# IOTBeev0_11.net
KiCad netlist of a schematic drawn in EAGLE
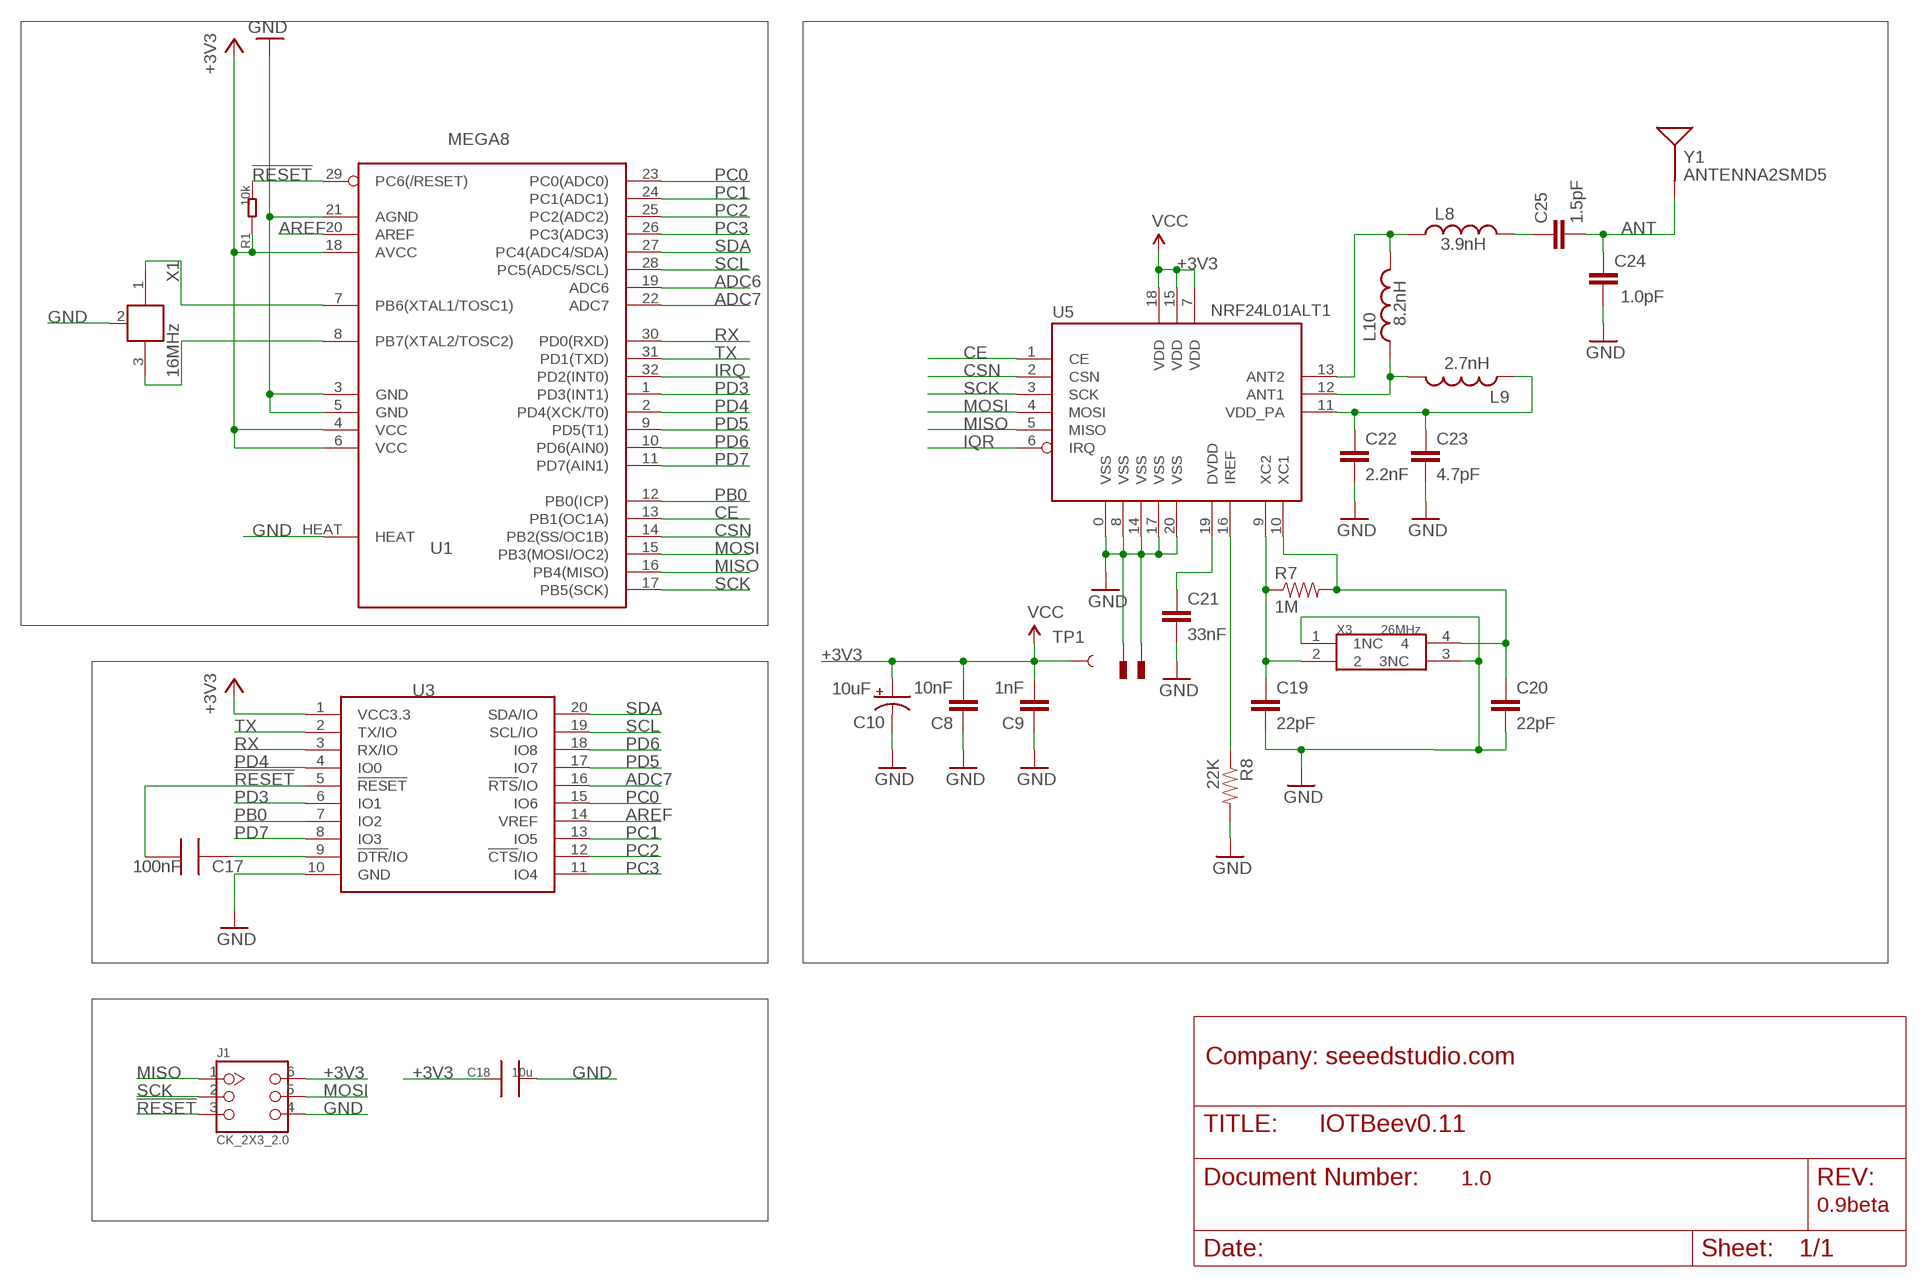
[diagram p0: schematic, sheet 1]

(export (version "E")
  (design (tool "Eeschema 10.0.6"))
  (components
    (comp (ref "C8")
      (value "10nF")
      (footprint "eagle-import:0402-CAP")
      (libsource (lib "eagle-import") (part "CAP0402-CAP"))
    )
    (comp (ref "C9")
      (value "1nF")
      (footprint "eagle-import:0402-CAP")
      (libsource (lib "eagle-import") (part "CAP0402-CAP"))
    )
    (comp (ref "C10")
      (value "10uF")
      (footprint "eagle-import:EIA3528")
      (libsource (lib "eagle-import") (part "CAP_POL3528"))
    )
    (comp (ref "C17")
      (value "100nF")
      (footprint "eagle-import:0603_S")
      (libsource (lib "eagle-import") (part "C0603_S"))
    )
    (comp (ref "C18")
      (value "10u")
      (footprint "eagle-import:0805")
      (libsource (lib "eagle-import") (part "C0805"))
    )
    (comp (ref "C19")
      (value "22pF")
      (footprint "eagle-import:0402-CAP")
      (libsource (lib "eagle-import") (part "CAP0402-CAP"))
    )
    (comp (ref "C20")
      (value "22pF")
      (footprint "eagle-import:0402-CAP")
      (libsource (lib "eagle-import") (part "CAP0402-CAP"))
    )
    (comp (ref "C21")
      (value "33nF")
      (footprint "eagle-import:0402-CAP")
      (libsource (lib "eagle-import") (part "CAP0402-CAP"))
    )
    (comp (ref "C22")
      (value "2.2nF")
      (footprint "eagle-import:0402-CAP")
      (libsource (lib "eagle-import") (part "CAP0402-CAP"))
    )
    (comp (ref "C23")
      (value "4.7pF")
      (footprint "eagle-import:0402-CAP")
      (libsource (lib "eagle-import") (part "CAP0402-CAP"))
    )
    (comp (ref "C24")
      (value "1.0pF")
      (footprint "eagle-import:0402-CAP")
      (libsource (lib "eagle-import") (part "CAP0402-CAP"))
    )
    (comp (ref "C25")
      (value "1.5pF")
      (footprint "eagle-import:0402-CAP")
      (libsource (lib "eagle-import") (part "CAP0402-CAP"))
    )
    (comp (ref "J1")
      (value "CK_2X3_2.0")
      (footprint "eagle-import:CK_2X3_2.0")
      (libsource (lib "eagle-import") (part "CK_2X3_2.0"))
    )
    (comp (ref "L8")
      (value "3.9nH")
      (footprint "eagle-import:C0402")
      (libsource (lib "eagle-import") (part "INDUCTOR0402"))
    )
    (comp (ref "L9")
      (value "2.7nH")
      (footprint "eagle-import:C0402")
      (libsource (lib "eagle-import") (part "INDUCTOR0402"))
    )
    (comp (ref "L10")
      (value "8.2nH")
      (footprint "eagle-import:C0402")
      (libsource (lib "eagle-import") (part "INDUCTOR0402"))
    )
    (comp (ref "R1")
      (value "10k")
      (footprint "eagle-import:0603_S")
      (libsource (lib "eagle-import") (part "R0603_S"))
    )
    (comp (ref "R7")
      (value "1M")
      (footprint "eagle-import:0402-RES")
      (libsource (lib "eagle-import") (part "RESISTOR0402-RES"))
    )
    (comp (ref "R8")
      (value "22K")
      (footprint "eagle-import:0402-RES")
      (libsource (lib "eagle-import") (part "RESISTOR0402-RES"))
    )
    (comp (ref "TP1")
      (value "TEST-POINT3X5")
      (footprint "eagle-import:PAD.03X.05")
      (libsource (lib "eagle-import") (part "TEST-POINT3X5"))
    )
    (comp (ref "U$2")
      (value "PAD")
      (footprint "eagle-import:PAD-0.008")
      (libsource (lib "eagle-import") (part "PAD"))
    )
    (comp (ref "U$4")
      (value "PAD")
      (footprint "eagle-import:PAD-0.008")
      (libsource (lib "eagle-import") (part "PAD"))
    )
    (comp (ref "U1")
      (value "MEGA8")
      (footprint "eagle-import:MLF32X")
      (libsource (lib "eagle-import") (part "MEGA8"))
    )
    (comp (ref "U3")
      (value "BEE-OPENBEE-BTSMD")
      (footprint "eagle-import:20P-SMD-2.0-BT")
      (libsource (lib "eagle-import") (part "BEE-OPENBEE-BTSMD"))
    )
    (comp (ref "U5")
      (value "NRF24L01ALT1")
      (footprint "eagle-import:QFN20_ALT1")
      (libsource (lib "eagle-import") (part "NRF24L01ALT1"))
    )
    (comp (ref "X1")
      (value "16MHz")
      (footprint "eagle-import:XTAL_3X2")
      (libsource (lib "eagle-import") (part "XTAL_NCVER"))
    )
    (comp (ref "X3")
      (value "26MHz")
      (footprint "eagle-import:X3225")
      (libsource (lib "eagle-import") (part "XTAL_SMD_3225"))
    )
    (comp (ref "Y1")
      (value "ANTENNA2SMD5")
      (footprint "eagle-import:ANTENNA-CHIP5")
      (libsource (lib "eagle-import") (part "ANTENNA2SMD5"))
    )
  )
  (nets
    (net (code "1") (name "+3V3") (class "Default")
      (node (ref "C10") (pin "A") (pinfunction "+_A") (pintype "passive"))
      (node (ref "C18") (pin "1") (pinfunction "1_1") (pintype "bidirectional"))
      (node (ref "C8") (pin "2") (pinfunction "2_2") (pintype "passive"))
      (node (ref "C9") (pin "2") (pinfunction "2_2") (pintype "passive"))
      (node (ref "J1") (pin "6") (pinfunction "P$6_6") (pintype "bidirectional"))
      (node (ref "R1") (pin "1") (pinfunction "1_1") (pintype "bidirectional"))
      (node (ref "TP1") (pin "P$1") (pinfunction "1_P$1") (pintype "bidirectional"))
      (node (ref "U1") (pin "18") (pinfunction "AVCC_18") (pintype "bidirectional"))
      (node (ref "U1") (pin "4") (pinfunction "VCC_4") (pintype "bidirectional"))
      (node (ref "U1") (pin "6") (pinfunction "VCC_6") (pintype "bidirectional"))
      (node (ref "U3") (pin "1") (pinfunction "VCC3.3_1") (pintype "bidirectional"))
      (node (ref "U5") (pin "15") (pinfunction "VDD_15") (pintype "power_in"))
      (node (ref "U5") (pin "18") (pinfunction "VDD_18") (pintype "power_in"))
      (node (ref "U5") (pin "7") (pinfunction "VDD_7") (pintype "power_in"))
    )
    (net (code "2") (name "/ADC6") (class "Default")
      (node (ref "U1") (pin "19") (pinfunction "ADC6_19") (pintype "bidirectional"))
    )
    (net (code "3") (name "/ADC7") (class "Default")
      (node (ref "U1") (pin "22") (pinfunction "ADC7_22") (pintype "bidirectional"))
      (node (ref "U3") (pin "16") (pinfunction "~{RTS}/IO_16") (pintype "bidirectional"))
    )
    (net (code "4") (name "/ANT") (class "Default")
      (node (ref "C24") (pin "2") (pinfunction "2_2") (pintype "passive"))
      (node (ref "C25") (pin "2") (pinfunction "2_2") (pintype "passive"))
      (node (ref "Y1") (pin "FEED") (pinfunction "SIGNAL_FEED") (pintype "bidirectional"))
    )
    (net (code "5") (name "/AREF") (class "Default")
      (node (ref "U1") (pin "20") (pinfunction "AREF_20") (pintype "bidirectional"))
      (node (ref "U3") (pin "14") (pinfunction "VREF_14") (pintype "bidirectional"))
    )
    (net (code "6") (name "/CE") (class "Default")
      (node (ref "U1") (pin "13") (pinfunction "PB1(OC1A)_13") (pintype "bidirectional"))
      (node (ref "U5") (pin "1") (pinfunction "CE_1") (pintype "input"))
    )
    (net (code "7") (name "/CSN") (class "Default")
      (node (ref "U1") (pin "14") (pinfunction "PB2(SS/OC1B)_14") (pintype "bidirectional"))
      (node (ref "U5") (pin "2") (pinfunction "CSN_2") (pintype "input"))
    )
    (net (code "8") (name "/IQR") (class "Default")
      (node (ref "U5") (pin "6") (pinfunction "IRQ_6") (pintype "output"))
    )
    (net (code "9") (name "/IRQ") (class "Default")
      (node (ref "U1") (pin "32") (pinfunction "PD2(INT0)_32") (pintype "bidirectional"))
    )
    (net (code "10") (name "/MISO") (class "Default")
      (node (ref "J1") (pin "1") (pinfunction "P$1_1") (pintype "bidirectional"))
      (node (ref "U1") (pin "16") (pinfunction "PB4(MISO)_16") (pintype "bidirectional"))
      (node (ref "U5") (pin "5") (pinfunction "MISO_5") (pintype "output"))
    )
    (net (code "11") (name "/MOSI") (class "Default")
      (node (ref "J1") (pin "5") (pinfunction "P$5_5") (pintype "bidirectional"))
      (node (ref "U1") (pin "15") (pinfunction "PB3(MOSI/OC2)_15") (pintype "bidirectional"))
      (node (ref "U5") (pin "4") (pinfunction "MOSI_4") (pintype "input"))
    )
    (net (code "12") (name "/PB0") (class "Default")
      (node (ref "U1") (pin "12") (pinfunction "PB0(ICP)_12") (pintype "bidirectional"))
      (node (ref "U3") (pin "7") (pinfunction "IO2_7") (pintype "bidirectional"))
    )
    (net (code "13") (name "/PC0") (class "Default")
      (node (ref "U1") (pin "23") (pinfunction "PC0(ADC0)_23") (pintype "bidirectional"))
      (node (ref "U3") (pin "15") (pinfunction "IO6_15") (pintype "bidirectional"))
    )
    (net (code "14") (name "/PC1") (class "Default")
      (node (ref "U1") (pin "24") (pinfunction "PC1(ADC1)_24") (pintype "bidirectional"))
      (node (ref "U3") (pin "13") (pinfunction "IO5_13") (pintype "bidirectional"))
    )
    (net (code "15") (name "/PC2") (class "Default")
      (node (ref "U1") (pin "25") (pinfunction "PC2(ADC2)_25") (pintype "bidirectional"))
      (node (ref "U3") (pin "12") (pinfunction "~{CTS}/IO_12") (pintype "bidirectional"))
    )
    (net (code "16") (name "/PC3") (class "Default")
      (node (ref "U1") (pin "26") (pinfunction "PC3(ADC3)_26") (pintype "bidirectional"))
      (node (ref "U3") (pin "11") (pinfunction "IO4_11") (pintype "bidirectional"))
    )
    (net (code "17") (name "/PD3") (class "Default")
      (node (ref "U1") (pin "1") (pinfunction "PD3(INT1)_1") (pintype "bidirectional"))
      (node (ref "U3") (pin "6") (pinfunction "IO1_6") (pintype "bidirectional"))
    )
    (net (code "18") (name "/PD4") (class "Default")
      (node (ref "U1") (pin "2") (pinfunction "PD4(XCK/T0)_2") (pintype "bidirectional"))
      (node (ref "U3") (pin "4") (pinfunction "IO0_4") (pintype "bidirectional"))
    )
    (net (code "19") (name "/PD5") (class "Default")
      (node (ref "U1") (pin "9") (pinfunction "PD5(T1)_9") (pintype "bidirectional"))
      (node (ref "U3") (pin "17") (pinfunction "IO7_17") (pintype "bidirectional"))
    )
    (net (code "20") (name "/PD6") (class "Default")
      (node (ref "U1") (pin "10") (pinfunction "PD6(AIN0)_10") (pintype "bidirectional"))
      (node (ref "U3") (pin "18") (pinfunction "IO8_18") (pintype "bidirectional"))
    )
    (net (code "21") (name "/PD7") (class "Default")
      (node (ref "U1") (pin "11") (pinfunction "PD7(AIN1)_11") (pintype "bidirectional"))
      (node (ref "U3") (pin "8") (pinfunction "IO3_8") (pintype "bidirectional"))
    )
    (net (code "22") (name "/RX") (class "Default")
      (node (ref "U1") (pin "30") (pinfunction "PD0(RXD)_30") (pintype "bidirectional"))
      (node (ref "U3") (pin "3") (pinfunction "RX/IO_3") (pintype "bidirectional"))
    )
    (net (code "23") (name "/SCK") (class "Default")
      (node (ref "J1") (pin "2") (pinfunction "P$2_2") (pintype "bidirectional"))
      (node (ref "U1") (pin "17") (pinfunction "PB5(SCK)_17") (pintype "bidirectional"))
      (node (ref "U5") (pin "3") (pinfunction "SCK_3") (pintype "input"))
    )
    (net (code "24") (name "/SCL") (class "Default")
      (node (ref "U1") (pin "28") (pinfunction "PC5(ADC5/SCL)_28") (pintype "bidirectional"))
      (node (ref "U3") (pin "19") (pinfunction "SCL/IO_19") (pintype "bidirectional"))
    )
    (net (code "25") (name "/SDA") (class "Default")
      (node (ref "U1") (pin "27") (pinfunction "PC4(ADC4/SDA)_27") (pintype "bidirectional"))
      (node (ref "U3") (pin "20") (pinfunction "SDA/IO_20") (pintype "bidirectional"))
    )
    (net (code "26") (name "/TX") (class "Default")
      (node (ref "U1") (pin "31") (pinfunction "PD1(TXD)_31") (pintype "bidirectional"))
      (node (ref "U3") (pin "2") (pinfunction "TX/IO_2") (pintype "bidirectional"))
    )
    (net (code "27") (name "/~{RESET}") (class "Default")
      (node (ref "C17") (pin "2") (pinfunction "2_2") (pintype "bidirectional"))
      (node (ref "J1") (pin "3") (pinfunction "P$3_3") (pintype "bidirectional"))
      (node (ref "R1") (pin "2") (pinfunction "2_2") (pintype "bidirectional"))
      (node (ref "U1") (pin "29") (pinfunction "PC6(/RESET)_29") (pintype "bidirectional"))
      (node (ref "U3") (pin "5") (pinfunction "~{RESET}_5") (pintype "bidirectional"))
    )
    (net (code "28") (name "GND") (class "Default")
      (node (ref "C10") (pin "C") (pinfunction "-_C") (pintype "passive"))
      (node (ref "C18") (pin "2") (pinfunction "2_2") (pintype "bidirectional"))
      (node (ref "C19") (pin "2") (pinfunction "2_2") (pintype "passive"))
      (node (ref "C20") (pin "2") (pinfunction "2_2") (pintype "passive"))
      (node (ref "C21") (pin "2") (pinfunction "2_2") (pintype "passive"))
      (node (ref "C22") (pin "2") (pinfunction "2_2") (pintype "passive"))
      (node (ref "C23") (pin "2") (pinfunction "2_2") (pintype "passive"))
      (node (ref "C24") (pin "1") (pinfunction "1_1") (pintype "passive"))
      (node (ref "C8") (pin "1") (pinfunction "1_1") (pintype "passive"))
      (node (ref "C9") (pin "1") (pinfunction "1_1") (pintype "passive"))
      (node (ref "J1") (pin "4") (pinfunction "P$4_4") (pintype "bidirectional"))
      (node (ref "R8") (pin "2") (pinfunction "2_2") (pintype "passive"))
      (node (ref "U$2") (pin "P$1") (pinfunction "P$1_P$1") (pintype "bidirectional"))
      (node (ref "U$4") (pin "P$1") (pinfunction "P$1_P$1") (pintype "bidirectional"))
      (node (ref "U1") (pin "21") (pinfunction "AGND_21") (pintype "bidirectional"))
      (node (ref "U1") (pin "3") (pinfunction "GND_3") (pintype "bidirectional"))
      (node (ref "U1") (pin "5") (pinfunction "GND_5") (pintype "bidirectional"))
      (node (ref "U1") (pin "HEAT") (pinfunction "HEAT_HEAT") (pintype "bidirectional"))
      (node (ref "U3") (pin "10") (pinfunction "GND_10") (pintype "bidirectional"))
      (node (ref "U5") (pin "0") (pinfunction "VSS_0") (pintype "power_in"))
      (node (ref "U5") (pin "14") (pinfunction "VSS_14") (pintype "power_in"))
      (node (ref "U5") (pin "17") (pinfunction "VSS_17") (pintype "power_in"))
      (node (ref "U5") (pin "20") (pinfunction "VSS_20") (pintype "power_in"))
      (node (ref "U5") (pin "8") (pinfunction "VSS_8") (pintype "power_in"))
      (node (ref "X1") (pin "2") (pinfunction "GND_2") (pintype "bidirectional"))
      (node (ref "X3") (pin "1") (pinfunction "1NC_1") (pintype "bidirectional"))
      (node (ref "X3") (pin "3") (pinfunction "3NC_3") (pintype "bidirectional"))
    )
    (net (code "29") (name "Net-(C25-Pad1)") (class "Default")
      (node (ref "C25") (pin "1") (pinfunction "1_1") (pintype "passive"))
      (node (ref "L8") (pin "2") (pinfunction "2_2") (pintype "passive"))
    )
    (net (code "30") (name "Net-(U1-PB6(XTAL1{slash}TOSC1))") (class "Default")
      (node (ref "U1") (pin "7") (pinfunction "PB6(XTAL1/TOSC1)_7") (pintype "bidirectional"))
      (node (ref "X1") (pin "1") (pinfunction "1_1") (pintype "bidirectional"))
    )
    (net (code "31") (name "Net-(U1-PB7(XTAL2{slash}TOSC2))") (class "Default")
      (node (ref "U1") (pin "8") (pinfunction "PB7(XTAL2/TOSC2)_8") (pintype "bidirectional"))
      (node (ref "X1") (pin "3") (pinfunction "2_3") (pintype "bidirectional"))
    )
    (net (code "32") (name "Net-(U3-~{DTR}{slash}IO)") (class "Default")
      (node (ref "C17") (pin "1") (pinfunction "1_1") (pintype "bidirectional"))
      (node (ref "U3") (pin "9") (pinfunction "~{DTR}/IO_9") (pintype "bidirectional"))
    )
    (net (code "33") (name "Net-(U5-ANT1)") (class "Default")
      (node (ref "L10") (pin "1") (pinfunction "1_1") (pintype "passive"))
      (node (ref "L9") (pin "2") (pinfunction "2_2") (pintype "passive"))
      (node (ref "U5") (pin "12") (pinfunction "ANT1_12") (pintype "output"))
    )
    (net (code "34") (name "Net-(U5-ANT2)") (class "Default")
      (node (ref "L10") (pin "2") (pinfunction "2_2") (pintype "passive"))
      (node (ref "L8") (pin "1") (pinfunction "1_1") (pintype "passive"))
      (node (ref "U5") (pin "13") (pinfunction "ANT2_13") (pintype "output"))
    )
    (net (code "35") (name "Net-(U5-DVDD)") (class "Default")
      (node (ref "C21") (pin "1") (pinfunction "1_1") (pintype "passive"))
      (node (ref "U5") (pin "19") (pinfunction "DVDD_19") (pintype "power_in"))
    )
    (net (code "36") (name "Net-(U5-IREF)") (class "Default")
      (node (ref "R8") (pin "1") (pinfunction "1_1") (pintype "passive"))
      (node (ref "U5") (pin "16") (pinfunction "IREF_16") (pintype "input"))
    )
    (net (code "37") (name "Net-(U5-VDD_PA)") (class "Default")
      (node (ref "C22") (pin "1") (pinfunction "1_1") (pintype "passive"))
      (node (ref "C23") (pin "1") (pinfunction "1_1") (pintype "passive"))
      (node (ref "L9") (pin "1") (pinfunction "1_1") (pintype "passive"))
      (node (ref "U5") (pin "11") (pinfunction "VDD_PA_11") (pintype "power_in"))
    )
    (net (code "38") (name "Net-(U5-XC1)") (class "Default")
      (node (ref "C20") (pin "1") (pinfunction "1_1") (pintype "passive"))
      (node (ref "R7") (pin "2") (pinfunction "2_2") (pintype "passive"))
      (node (ref "U5") (pin "10") (pinfunction "XC1_10") (pintype "input"))
      (node (ref "X3") (pin "4") (pinfunction "4_4") (pintype "bidirectional"))
    )
    (net (code "39") (name "Net-(U5-XC2)") (class "Default")
      (node (ref "C19") (pin "1") (pinfunction "1_1") (pintype "passive"))
      (node (ref "R7") (pin "1") (pinfunction "1_1") (pintype "passive"))
      (node (ref "U5") (pin "9") (pinfunction "XC2_9") (pintype "input"))
      (node (ref "X3") (pin "2") (pinfunction "2_2") (pintype "bidirectional"))
    )
  )
)
